# 1_POWER.net
KiCad netlist of a schematic drawn in Altium Designer
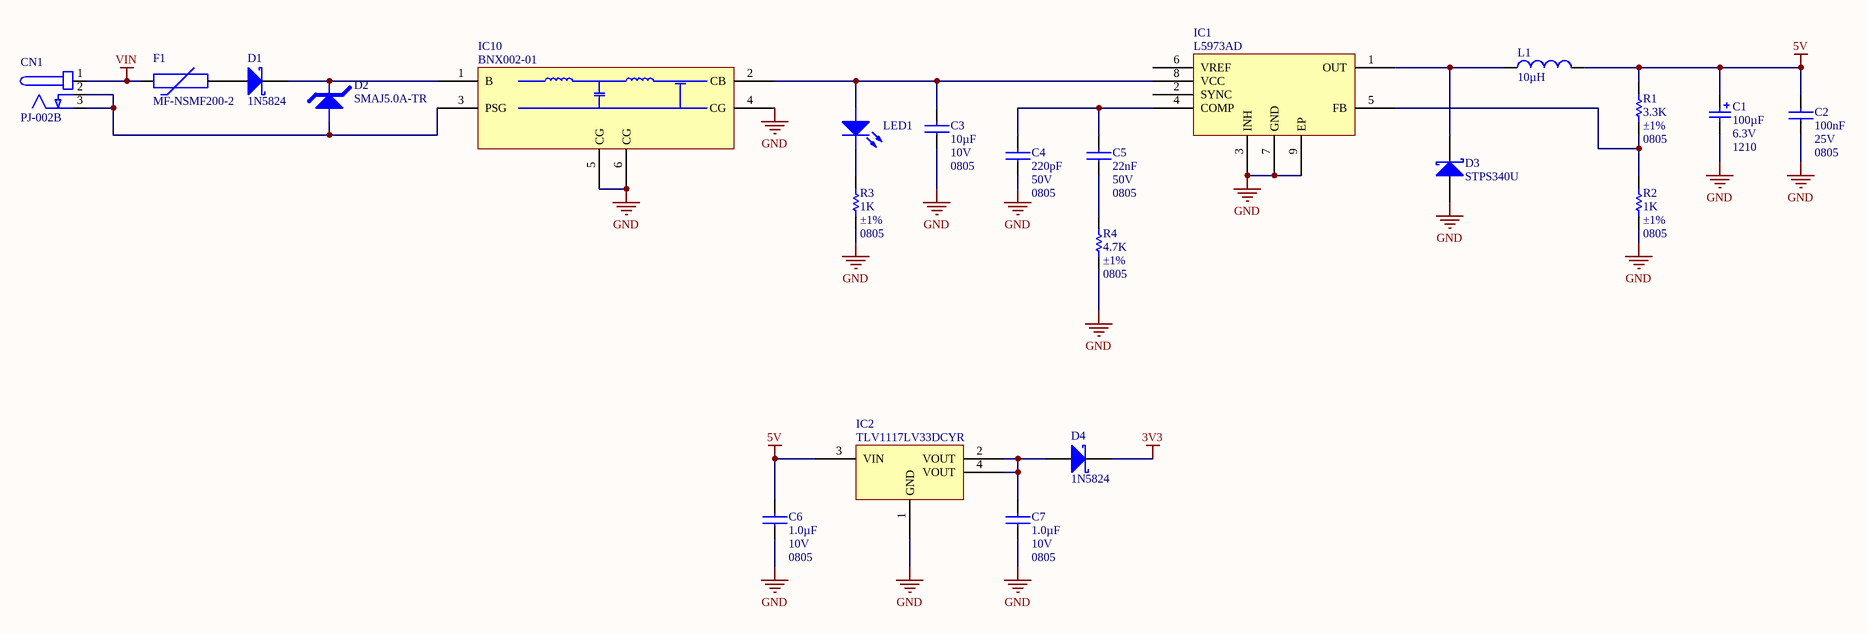
[diagram p0: 1.POWER.SchDoc]

(export (version "E")
  (design (tool "Eeschema 10.0.6"))
  (components
    (comp (ref "C1")
      (value "CAP_P")
      (footprint "CAPMP3528X19N_EIA-1210_CASE-B")
      (description "CAP TANT 100UF 6.3V 20% 1210")
      (fields
        (field (name "PART NUMBER") "SCAP01400007")
        (field (name "CAPACITANCE") "100µF")
        (field (name "TOLERANCE") "±20%")
        (field (name "VOLTAGE - RATED") "6.3V")
        (field (name "PACKAGE / CASE") "1210")
      )
      (libsource (lib "ComponentDatabase") (part "CAP_P"))
    )
    (comp (ref "C2")
      (value "CAP_NP")
      (footprint "CAPC2012X100N_EIA0805")
      (description "CAP CER 0.1UF 25V X7R 0805")
      (fields
        (field (name "PART NUMBER") "SCAP00300093")
        (field (name "CAPACITANCE") "100nF")
        (field (name "TOLERANCE") "±10%")
        (field (name "VOLTAGE - RATED") "25V")
        (field (name "PACKAGE / CASE") "0805")
      )
      (libsource (lib "ComponentDatabase") (part "CAP_NP"))
    )
    (comp (ref "C3")
      (value "CAP_NP")
      (footprint "CAPC2012X100N_EIA0805")
      (description "CAP CER 10UF 10V X5R 0805")
      (fields
        (field (name "PART NUMBER") "SCAP00300106")
        (field (name "CAPACITANCE") "10µF")
        (field (name "TOLERANCE") "±10%")
        (field (name "VOLTAGE - RATED") "10V")
        (field (name "PACKAGE / CASE") "0805")
      )
      (libsource (lib "ComponentDatabase") (part "CAP_NP"))
    )
    (comp (ref "C4")
      (value "CAP_NP")
      (footprint "CAPC2012X100N_EIA0805")
      (description "CAP CER 220PF 50V X7R 0805")
      (fields
        (field (name "PART NUMBER") "SCAP00300066")
        (field (name "CAPACITANCE") "220pF")
        (field (name "TOLERANCE") "±10%")
        (field (name "VOLTAGE - RATED") "50V")
        (field (name "PACKAGE / CASE") "0805")
      )
      (libsource (lib "ComponentDatabase") (part "CAP_NP"))
    )
    (comp (ref "C5")
      (value "CAP_NP")
      (footprint "CAPC2012X100N_EIA0805")
      (description "CAP CER 0.022UF 50V X7R 0805")
      (fields
        (field (name "PART NUMBER") "SCAP00300087")
        (field (name "CAPACITANCE") "22nF")
        (field (name "TOLERANCE") "±10%")
        (field (name "VOLTAGE - RATED") "50V")
        (field (name "PACKAGE / CASE") "0805")
      )
      (libsource (lib "ComponentDatabase") (part "CAP_NP"))
    )
    (comp (ref "C6")
      (value "CAP_NP")
      (footprint "CAPC2012X100N_EIA0805")
      (description "CAP CER 1UF 10V X7R 0805")
      (fields
        (field (name "PART NUMBER") "SCAP00300099")
        (field (name "CAPACITANCE") "1.0µF")
        (field (name "TOLERANCE") "±10%")
        (field (name "VOLTAGE - RATED") "10V")
        (field (name "PACKAGE / CASE") "0805")
      )
      (libsource (lib "ComponentDatabase") (part "CAP_NP"))
    )
    (comp (ref "C7")
      (value "CAP_NP")
      (footprint "CAPC2012X100N_EIA0805")
      (description "CAP CER 1UF 10V X7R 0805")
      (fields
        (field (name "PART NUMBER") "SCAP00300099")
        (field (name "CAPACITANCE") "1.0µF")
        (field (name "TOLERANCE") "±10%")
        (field (name "VOLTAGE - RATED") "10V")
        (field (name "PACKAGE / CASE") "0805")
      )
      (libsource (lib "ComponentDatabase") (part "CAP_NP"))
    )
    (comp (ref "CN1")
      (value "DC_JACK")
      (footprint "DC_JACK")
      (description "CONN POWER JACK MALE 2.5MM CLSD")
      (fields
        (field (name "PART NUMBER") "SCON00027")
        (field (name "VOLTAGE") "24VDC")
        (field (name "MANUFACTURER PART NUMBER") "PJ-002B")
      )
      (libsource (lib "ComponentDatabase") (part "DC_JACK"))
    )
    (comp (ref "D1")
      (value "1N5824")
      (footprint "DIOM4436X24N_DO-214AA_SMB")
      (description "DIODE SCHOTTKY 5A 40V SMA")
      (fields (field (name "PART NUMBER") "SSEM00019") (field (name "MANUFACTURER") "Micro Commercial Co"))
      (libsource (lib "ComponentDatabase") (part "DIODE_SCHOTTKY"))
    )
    (comp (ref "D2")
      (value "SMAJ5.0A-TR")
      (footprint "DIOM5126X26N_DO-214AC_SMA")
      (description "TVS DIODE 5VWM 13.4VC DO214AC")
      (fields (field (name "PART NUMBER") "SCP00004") (field (name "MANUFACTURER") "STMicroelectronics"))
      (libsource (lib "ComponentDatabase") (part "DIODE_TVS_UNI"))
    )
    (comp (ref "D3")
      (value "STPS340U")
      (footprint "DIOM4436X24N_DO-214AA_SMB")
      (description "DIODE SCHOTTKY 40V 3A SMB")
      (fields (field (name "PART NUMBER") "SSEM00020") (field (name "MANUFACTURER") "STMicroelectronics"))
      (libsource (lib "ComponentDatabase") (part "DIODE_SCHOTTKY"))
    )
    (comp (ref "D4")
      (value "1N5824")
      (footprint "DIOM4436X24N_DO-214AA_SMB")
      (description "DIODE SCHOTTKY 5A 40V SMA")
      (fields (field (name "PART NUMBER") "SSEM00019") (field (name "MANUFACTURER") "Micro Commercial Co"))
      (libsource (lib "ComponentDatabase") (part "DIODE_SCHOTTKY"))
    )
    (comp (ref "F1")
      (value "PTC")
      (footprint "FUSEC3216X16N")
      (description "FUSE RESETTABLE 2.0A HOLD SMD")
      (fields
        (field (name "PART NUMBER") "SCP00008")
        (field (name "MANUFACTURER") "Bourns Inc.")
        (field (name "MANUFACTURER PART NUMBER") "MF-NSMF200-2")
      )
      (libsource (lib "ComponentDatabase") (part "PTC"))
    )
    (comp (ref "IC1")
      (value "L5973AD")
      (footprint "SOP127P600X200_HS-9N")
      (description "IC REG BUCK ADJ 2A 8SOIC")
      (fields
        (field (name "PART NUMBER") "SIC00116")
        (field (name "MANUFACTURER PART NUMBER") "L5973AD")
        (field (name "MANUFACTURER") "STMicroelectronics")
      )
      (libsource (lib "ComponentDatabase") (part "L5973AD"))
    )
    (comp (ref "IC2")
      (value "TLV1117LV33DCYR")
      (footprint "SOT230P700X180-4N_[TEXAS]R-PDSO-G4")
      (description "IC REG LDO 3.3V 1A SOT223")
      (fields
        (field (name "PART NUMBER") "SIC00137")
        (field (name "MANUFACTURER PART NUMBER") "TLV1117LV33DCYR")
        (field (name "MANUFACTURER") "Texas Instruments")
      )
      (libsource (lib "ComponentDatabase") (part "TLV1117LV33DCYR"))
    )
    (comp (ref "IC10")
      (value "BNX002-01")
      (footprint "MURATA_BNX002-01")
      (description "FILTER LC TH")
      (fields
        (field (name "PART NUMBER") "SFIL00006")
        (field (name "MANUFACTURER") "Murata Electronics North America")
      )
      (libsource (lib "ComponentDatabase") (part "BNX002-01"))
    )
    (comp (ref "L1")
      (value "10µH")
      (footprint "TDK_SLF10145T-100M2R5-PF")
      (description "FIXED IND 10UH 2.5A 43.7 MOHM")
      (fields (field (name "PART NUMBER") "SIND00006") (field (name "TOLERANCE") "±20%"))
      (libsource (lib "ComponentDatabase") (part "INDUCTOR"))
    )
    (comp (ref "LED1")
      (value "LED")
      (footprint "LEDC2012X70N_EIA0805_GREEN")
      (description "LED GREEN CLEAR THIN 0805 SMD")
      (fields (field (name "PART NUMBER") "SOPT00002") (field (name "MANUFACTURER") "Lite-On Inc"))
      (libsource (lib "ComponentDatabase") (part "LED"))
    )
    (comp (ref "R1")
      (value "3.3K")
      (footprint "RESC2013X65N_EIA0805")
      (description "RES SMD 3.3K OHM 1% 1/8W 0805")
      (fields
        (field (name "PART NUMBER") "SRES03010086")
        (field (name "TOLERANCE") "±1%")
        (field (name "PACKAGE / CASE") "0805")
        (field (name "MANUFACTURER") "Yageo")
      )
      (libsource (lib "ComponentDatabase") (part "RES"))
    )
    (comp (ref "R2")
      (value "1K")
      (footprint "RESC2013X65N_EIA0805")
      (description "RES SMD 1K OHM 1% 1/8W 0805")
      (fields
        (field (name "PART NUMBER") "SRES03010074")
        (field (name "TOLERANCE") "±1%")
        (field (name "PACKAGE / CASE") "0805")
        (field (name "MANUFACTURER") "Yageo")
      )
      (libsource (lib "ComponentDatabase") (part "RES"))
    )
    (comp (ref "R3")
      (value "1K")
      (footprint "RESC2013X65N_EIA0805")
      (description "RES SMD 1K OHM 1% 1/8W 0805")
      (fields
        (field (name "PART NUMBER") "SRES03010074")
        (field (name "TOLERANCE") "±1%")
        (field (name "PACKAGE / CASE") "0805")
        (field (name "MANUFACTURER") "Yageo")
      )
      (libsource (lib "ComponentDatabase") (part "RES"))
    )
    (comp (ref "R4")
      (value "4.7K")
      (footprint "RESC2013X65N_EIA0805")
      (description "RES SMD 4.7K OHM 1% 1/8W 0805")
      (fields
        (field (name "PART NUMBER") "SRES03010090")
        (field (name "TOLERANCE") "±1%")
        (field (name "PACKAGE / CASE") "0805")
        (field (name "MANUFACTURER") "Yageo")
      )
      (libsource (lib "ComponentDatabase") (part "RES"))
    )
  )
  (nets
    (net (code "1") (name "3V3") (class "Default")
      (node (ref "D4") (pin "1") (pinfunction "1_1") (pintype "passive"))
    )
    (net (code "2") (name "5V") (class "Default")
      (node (ref "C1") (pin "1") (pinfunction "1_1") (pintype "passive"))
      (node (ref "C2") (pin "2") (pinfunction "2_2") (pintype "passive"))
      (node (ref "C6") (pin "2") (pinfunction "2_2") (pintype "passive"))
      (node (ref "IC2") (pin "3") (pinfunction "VIN_3") (pintype "passive"))
      (node (ref "L1") (pin "2") (pinfunction "2_2") (pintype "passive"))
      (node (ref "R1") (pin "1") (pinfunction "1_1") (pintype "passive"))
    )
    (net (code "3") (name "GND") (class "Default")
      (node (ref "C1") (pin "2") (pinfunction "2_2") (pintype "passive"))
      (node (ref "C2") (pin "1") (pinfunction "1_1") (pintype "passive"))
      (node (ref "C3") (pin "1") (pinfunction "1_1") (pintype "passive"))
      (node (ref "C4") (pin "1") (pinfunction "1_1") (pintype "passive"))
      (node (ref "C6") (pin "1") (pinfunction "1_1") (pintype "passive"))
      (node (ref "C7") (pin "1") (pinfunction "1_1") (pintype "passive"))
      (node (ref "D3") (pin "2") (pinfunction "2_2") (pintype "passive"))
      (node (ref "IC1") (pin "3") (pinfunction "INH_3") (pintype "power_in"))
      (node (ref "IC1") (pin "7") (pinfunction "GND_7") (pintype "power_in"))
      (node (ref "IC1") (pin "9") (pinfunction "EP_9") (pintype "power_in"))
      (node (ref "IC10") (pin "4") (pinfunction "CG_4") (pintype "power_in"))
      (node (ref "IC10") (pin "5") (pinfunction "CG_5") (pintype "power_in"))
      (node (ref "IC10") (pin "6") (pinfunction "CG_6") (pintype "power_in"))
      (node (ref "IC2") (pin "1") (pinfunction "GND_1") (pintype "passive"))
      (node (ref "R2") (pin "2") (pinfunction "2_2") (pintype "passive"))
      (node (ref "R3") (pin "2") (pinfunction "2_2") (pintype "passive"))
      (node (ref "R4") (pin "2") (pinfunction "2_2") (pintype "passive"))
    )
    (net (code "4") (name "Net-(C5-Pad1)") (class "Default")
      (node (ref "C5") (pin "1") (pinfunction "1_1") (pintype "passive"))
      (node (ref "R4") (pin "1") (pinfunction "1_1") (pintype "passive"))
    )
    (net (code "5") (name "Net-(C7-Pad2)") (class "Default")
      (node (ref "C7") (pin "2") (pinfunction "2_2") (pintype "passive"))
      (node (ref "D4") (pin "2") (pinfunction "2_2") (pintype "passive"))
      (node (ref "IC2") (pin "2") (pinfunction "VOUT_2") (pintype "passive"))
      (node (ref "IC2") (pin "4") (pinfunction "VOUT_4") (pintype "passive"))
    )
    (net (code "6") (name "Net-(D1-Pad2)") (class "Default")
      (node (ref "D1") (pin "2") (pinfunction "2_2") (pintype "passive"))
      (node (ref "F1") (pin "2") (pinfunction "2_2") (pintype "passive"))
    )
    (net (code "7") (name "Net-(IC1-COMP)") (class "Default")
      (node (ref "C4") (pin "2") (pinfunction "2_2") (pintype "passive"))
      (node (ref "C5") (pin "2") (pinfunction "2_2") (pintype "passive"))
      (node (ref "IC1") (pin "4") (pinfunction "COMP_4") (pintype "power_in"))
    )
    (net (code "8") (name "Net-(IC1-FB)") (class "Default")
      (node (ref "IC1") (pin "5") (pinfunction "FB_5") (pintype "power_in"))
      (node (ref "R1") (pin "2") (pinfunction "2_2") (pintype "passive"))
      (node (ref "R2") (pin "1") (pinfunction "1_1") (pintype "passive"))
    )
    (net (code "9") (name "Net-(IC1-OUT)") (class "Default")
      (node (ref "D3") (pin "1") (pinfunction "1_1") (pintype "passive"))
      (node (ref "IC1") (pin "1") (pinfunction "OUT_1") (pintype "power_in"))
      (node (ref "L1") (pin "1") (pinfunction "1_1") (pintype "passive"))
    )
    (net (code "10") (name "Net-(IC1-VCC)") (class "Default")
      (node (ref "C3") (pin "2") (pinfunction "2_2") (pintype "passive"))
      (node (ref "IC1") (pin "8") (pinfunction "VCC_8") (pintype "power_in"))
      (node (ref "IC10") (pin "2") (pinfunction "CB_2") (pintype "power_in"))
      (node (ref "LED1") (pin "2") (pinfunction "2_2") (pintype "passive"))
    )
    (net (code "11") (name "Net-(IC10-B)") (class "Default")
      (node (ref "D1") (pin "1") (pinfunction "1_1") (pintype "passive"))
      (node (ref "D2") (pin "1") (pinfunction "1_1") (pintype "passive"))
      (node (ref "IC10") (pin "1") (pinfunction "B_1") (pintype "power_in"))
    )
    (net (code "12") (name "Net-(IC10-PSG)") (class "Default")
      (node (ref "CN1") (pin "2") (pinfunction "GND_2") (pintype "passive"))
      (node (ref "CN1") (pin "3") (pinfunction "GND_3") (pintype "passive"))
      (node (ref "D2") (pin "2") (pinfunction "2_2") (pintype "passive"))
      (node (ref "IC10") (pin "3") (pinfunction "PSG_3") (pintype "power_in"))
    )
    (net (code "13") (name "Net-(LED1-Pad1)") (class "Default")
      (node (ref "LED1") (pin "1") (pinfunction "1_1") (pintype "passive"))
      (node (ref "R3") (pin "1") (pinfunction "1_1") (pintype "passive"))
    )
    (net (code "14") (name "VIN") (class "Default")
      (node (ref "CN1") (pin "1") (pinfunction "+_1") (pintype "passive"))
      (node (ref "F1") (pin "1") (pinfunction "1_1") (pintype "passive"))
    )
    (net (code "15") (name "unconnected-(IC1-SYNC-Pad2)") (class "Default")
      (node (ref "IC1") (pin "2") (pinfunction "SYNC_2") (pintype "power_in"))
    )
    (net (code "16") (name "unconnected-(IC1-VREF-Pad6)") (class "Default")
      (node (ref "IC1") (pin "6") (pinfunction "VREF_6") (pintype "power_in"))
    )
  )
)
